# T412_echohello.net
KiCad netlist of a schematic drawn in EAGLE
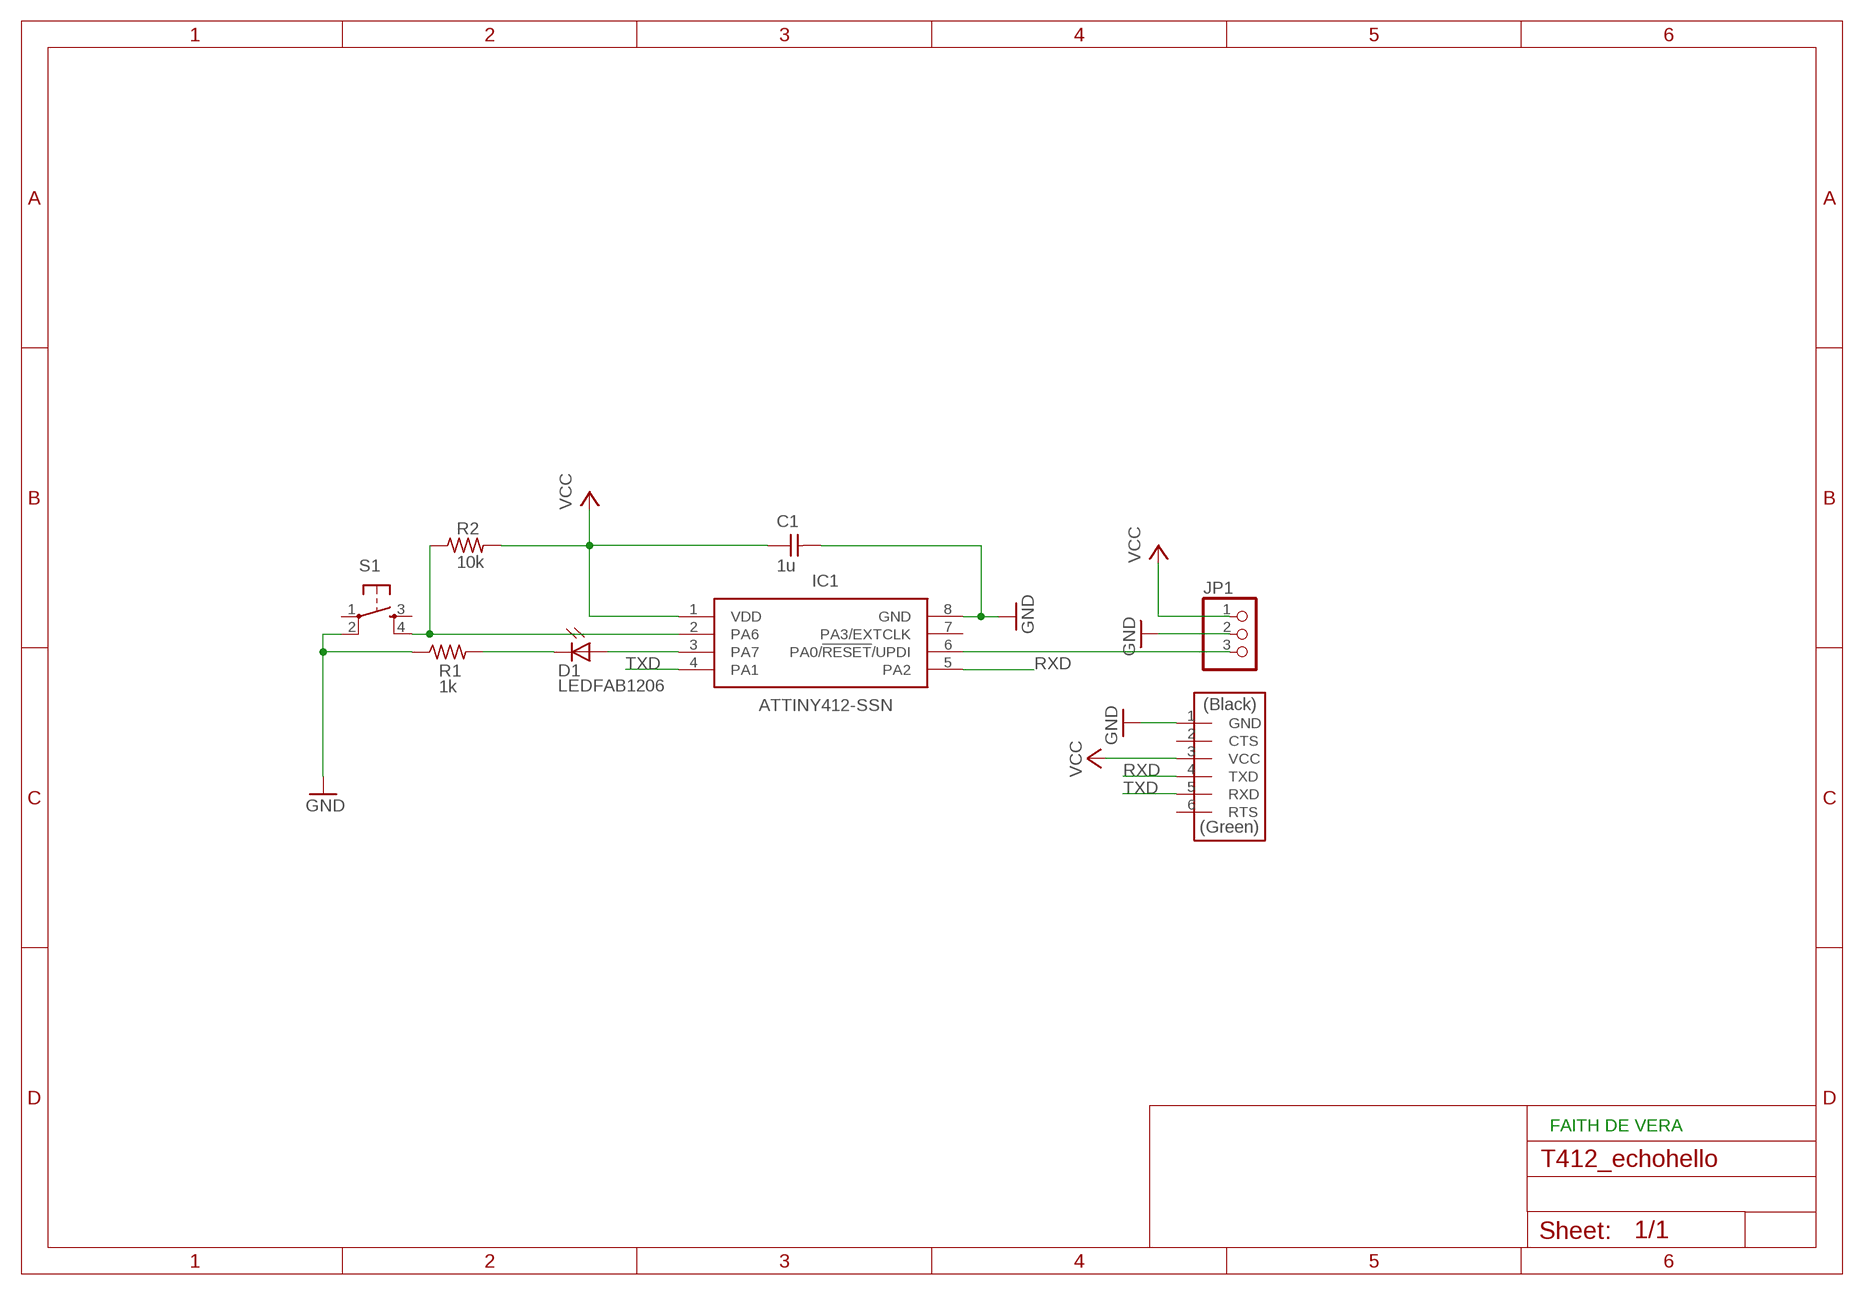
[diagram p0: schematic, sheet 1]

(export (version "E")
  (design (tool "Eeschema 10.0.6"))
  (components
    (comp (ref "C1")
      (value "1u")
      (footprint "eagle-import:C1206FAB")
      (libsource (lib "eagle-import") (part "CAP_UNPOLARIZEDFAB"))
    )
    (comp (ref "D1")
      (value "LEDFAB1206")
      (footprint "eagle-import:LED1206FAB")
      (libsource (lib "eagle-import") (part "LEDFAB1206"))
    )
    (comp (ref "IC1")
      (value "ATTINY412-SSN")
      (footprint "eagle-import:SOIC127P600X175-8N")
      (fields (field (name "MOUSER_PART_NUMBER") "579-ATTINY412-SSN"))
      (libsource (lib "eagle-import") (part "ATTINY412-SSN"))
    )
    (comp (ref "JP1")
      (value "PINHD-1X3")
      (footprint "eagle-import:1X03")
      (libsource (lib "eagle-import") (part "PINHD-1X3"))
    )
    (comp (ref "R1")
      (value "1k")
      (footprint "eagle-import:R1206FAB")
      (libsource (lib "eagle-import") (part "R1206FAB"))
    )
    (comp (ref "R2")
      (value "10k")
      (footprint "eagle-import:R1206FAB")
      (libsource (lib "eagle-import") (part "R1206FAB"))
    )
    (comp (ref "S1")
      (value "SW_SWITCH_TACTILE_6MM6MM_SWITCH")
      (footprint "eagle-import:6MM_SWITCH")
      (libsource (lib "eagle-import") (part "SW_SWITCH_TACTILE_6MM6MM_SWITCH"))
    )
    (comp (ref "U$2")
      (value "CONN_06_FTDI-SMD-HEADER")
      (footprint "eagle-import:1X06SMD")
      (libsource (lib "eagle-import") (part "CONN_06_FTDI-SMD-HEADER"))
    )
  )
  (nets
    (net (code "1") (name "/RXD") (class "Default")
      (node (ref "IC1") (pin "5") (pinfunction "PA2_5") (pintype "bidirectional"))
      (node (ref "U$2") (pin "4") (pinfunction "TXD_4") (pintype "bidirectional"))
    )
    (net (code "2") (name "/TXD") (class "Default")
      (node (ref "IC1") (pin "4") (pinfunction "PA1_4") (pintype "bidirectional"))
      (node (ref "U$2") (pin "5") (pinfunction "RXD_5") (pintype "bidirectional"))
    )
    (net (code "3") (name "GND") (class "Default")
      (node (ref "C1") (pin "2") (pinfunction "2_2") (pintype "passive"))
      (node (ref "IC1") (pin "8") (pinfunction "GND_8") (pintype "bidirectional"))
      (node (ref "JP1") (pin "2") (pinfunction "2_2") (pintype "passive"))
      (node (ref "R1") (pin "1") (pinfunction "1_1") (pintype "passive"))
      (node (ref "S1") (pin "2") (pinfunction "P1_2") (pintype "passive"))
      (node (ref "U$2") (pin "1") (pinfunction "GND_1") (pintype "bidirectional"))
    )
    (net (code "4") (name "Net-(D1-A)") (class "Default")
      (node (ref "D1") (pin "1") (pinfunction "A_1") (pintype "passive"))
      (node (ref "IC1") (pin "3") (pinfunction "PA7_3") (pintype "bidirectional"))
    )
    (net (code "5") (name "Net-(D1-C)") (class "Default")
      (node (ref "D1") (pin "2") (pinfunction "C_2") (pintype "passive"))
      (node (ref "R1") (pin "2") (pinfunction "2_2") (pintype "passive"))
    )
    (net (code "6") (name "Net-(IC1-PA0{slash}~{RESET}{slash}UPDI)") (class "Default")
      (node (ref "IC1") (pin "6") (pinfunction "PA0/~{RESET}/UPDI_6") (pintype "bidirectional"))
      (node (ref "JP1") (pin "3") (pinfunction "3_3") (pintype "passive"))
    )
    (net (code "7") (name "Net-(IC1-PA6)") (class "Default")
      (node (ref "IC1") (pin "2") (pinfunction "PA6_2") (pintype "bidirectional"))
      (node (ref "R2") (pin "1") (pinfunction "1_1") (pintype "passive"))
      (node (ref "S1") (pin "4") (pinfunction "S1_4") (pintype "passive"))
    )
    (net (code "8") (name "VCC") (class "Default")
      (node (ref "C1") (pin "1") (pinfunction "1_1") (pintype "passive"))
      (node (ref "IC1") (pin "1") (pinfunction "VDD_1") (pintype "bidirectional"))
      (node (ref "JP1") (pin "1") (pinfunction "1_1") (pintype "passive"))
      (node (ref "R2") (pin "2") (pinfunction "2_2") (pintype "passive"))
      (node (ref "U$2") (pin "3") (pinfunction "VCC_3") (pintype "bidirectional"))
    )
    (net (code "9") (name "unconnected-(IC1-PA3{slash}EXTCLK-Pad7)") (class "Default")
      (node (ref "IC1") (pin "7") (pinfunction "PA3/EXTCLK_7") (pintype "bidirectional"))
    )
    (net (code "10") (name "unconnected-(S1-P-Pad1)") (class "Default")
      (node (ref "S1") (pin "1") (pinfunction "P_1") (pintype "passive"))
    )
    (net (code "11") (name "unconnected-(S1-S-Pad3)") (class "Default")
      (node (ref "S1") (pin "3") (pinfunction "S_3") (pintype "passive"))
    )
    (net (code "12") (name "unconnected-(U$2-CTS-Pad2)") (class "Default")
      (node (ref "U$2") (pin "2") (pinfunction "CTS_2") (pintype "bidirectional"))
    )
    (net (code "13") (name "unconnected-(U$2-RTS-Pad6)") (class "Default")
      (node (ref "U$2") (pin "6") (pinfunction "RTS_6") (pintype "bidirectional"))
    )
  )
)
